# shieldSchematic.net
KiCad netlist of a schematic drawn in EAGLE
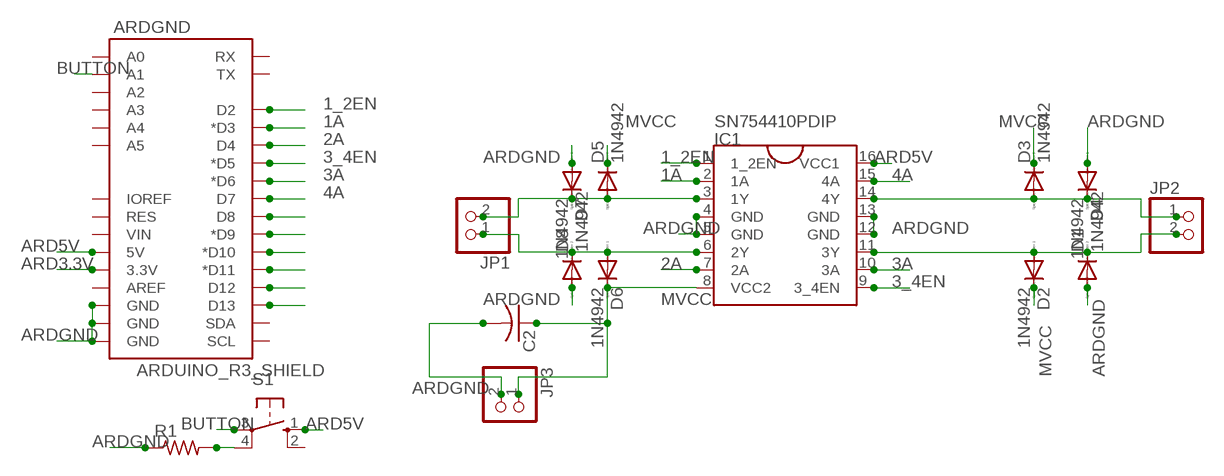
[diagram p0: schematic, sheet 1]

(export (version "E")
  (design (tool "Eeschema 10.0.6"))
  (components
    (comp (ref "ARDGND")
      (value "ARDUINO_R3_SHIELD")
      (footprint "eagle-import:UNO_R3_SHIELD")
      (libsource (lib "eagle-import") (part "ARDUINO_R3_SHIELD"))
    )
    (comp (ref "C2")
      (value "C-US025-024X044")
      (footprint "eagle-import:C025-024X044")
      (libsource (lib "eagle-import") (part "C-US025-024X044"))
    )
    (comp (ref "D1")
      (value "1N4942")
      (footprint "eagle-import:DO41-10")
      (libsource (lib "eagle-import") (part "1N4942"))
    )
    (comp (ref "D2")
      (value "1N4942")
      (footprint "eagle-import:DO41-10")
      (libsource (lib "eagle-import") (part "1N4942"))
    )
    (comp (ref "D3")
      (value "1N4942")
      (footprint "eagle-import:DO41-10")
      (libsource (lib "eagle-import") (part "1N4942"))
    )
    (comp (ref "D4")
      (value "1N4942")
      (footprint "eagle-import:DO41-10")
      (libsource (lib "eagle-import") (part "1N4942"))
    )
    (comp (ref "D5")
      (value "1N4942")
      (footprint "eagle-import:DO41-10")
      (libsource (lib "eagle-import") (part "1N4942"))
    )
    (comp (ref "D6")
      (value "1N4942")
      (footprint "eagle-import:DO41-10")
      (libsource (lib "eagle-import") (part "1N4942"))
    )
    (comp (ref "D7")
      (value "1N4942")
      (footprint "eagle-import:DO41-10")
      (libsource (lib "eagle-import") (part "1N4942"))
    )
    (comp (ref "D8")
      (value "1N4942")
      (footprint "eagle-import:DO41-10")
      (libsource (lib "eagle-import") (part "1N4942"))
    )
    (comp (ref "IC1")
      (value "SN754410PDIP")
      (footprint "eagle-import:DIL16")
      (libsource (lib "eagle-import") (part "SN754410PDIP"))
    )
    (comp (ref "JP1")
      (value "PINHD-1X2")
      (footprint "eagle-import:1X02")
      (libsource (lib "eagle-import") (part "PINHD-1X2"))
    )
    (comp (ref "JP2")
      (value "PINHD-1X2")
      (footprint "eagle-import:1X02")
      (libsource (lib "eagle-import") (part "PINHD-1X2"))
    )
    (comp (ref "JP3")
      (value "PINHD-1X2")
      (footprint "eagle-import:1X02")
      (libsource (lib "eagle-import") (part "PINHD-1X2"))
    )
    (comp (ref "R1")
      (value "R-US_0207/10")
      (footprint "eagle-import:0207_10")
      (libsource (lib "eagle-import") (part "R-US_0207/10"))
    )
    (comp (ref "S1")
      (value "40-XX")
      (footprint "eagle-import:B3F-40XX")
      (fields (field (name "MF") "OMRON COMPONENTS USA") (field (name "MPN") "B3F-4000"))
      (libsource (lib "eagle-import") (part "40-XX"))
    )
  )
  (nets
    (net (code "1") (name "/1A") (class "Default")
      (node (ref "ARDGND") (pin "D3") (pinfunction "*D3_D3") (pintype "bidirectional"))
      (node (ref "IC1") (pin "2") (pinfunction "1A_2") (pintype "bidirectional"))
    )
    (net (code "2") (name "/1_2EN") (class "Default")
      (node (ref "ARDGND") (pin "D2") (pinfunction "D2_D2") (pintype "bidirectional"))
      (node (ref "IC1") (pin "1") (pinfunction "1_2EN_1") (pintype "bidirectional"))
    )
    (net (code "3") (name "/2A") (class "Default")
      (node (ref "ARDGND") (pin "D4") (pinfunction "D4_D4") (pintype "bidirectional"))
      (node (ref "IC1") (pin "7") (pinfunction "2A_7") (pintype "bidirectional"))
    )
    (net (code "4") (name "/3A") (class "Default")
      (node (ref "ARDGND") (pin "D6") (pinfunction "*D6_D6") (pintype "bidirectional"))
      (node (ref "IC1") (pin "10") (pinfunction "3A_10") (pintype "bidirectional"))
    )
    (net (code "5") (name "/3_4EN") (class "Default")
      (node (ref "ARDGND") (pin "D5") (pinfunction "*D5_D5") (pintype "bidirectional"))
      (node (ref "IC1") (pin "9") (pinfunction "3_4EN_9") (pintype "bidirectional"))
    )
    (net (code "6") (name "/4A") (class "Default")
      (node (ref "ARDGND") (pin "D7") (pinfunction "D7_D7") (pintype "bidirectional"))
      (node (ref "IC1") (pin "15") (pinfunction "4A_15") (pintype "bidirectional"))
    )
    (net (code "7") (name "/ARD3.3V") (class "Default")
      (node (ref "ARDGND") (pin "3.3V") (pinfunction "3.3V_3.3V") (pintype "bidirectional"))
    )
    (net (code "8") (name "/ARD5V") (class "Default")
      (node (ref "ARDGND") (pin "5V") (pinfunction "5V_5V") (pintype "bidirectional"))
      (node (ref "IC1") (pin "16") (pinfunction "VCC1_16") (pintype "bidirectional"))
      (node (ref "S1") (pin "1") (pinfunction "S_1") (pintype "passive"))
    )
    (net (code "9") (name "/ARDGND") (class "Default")
      (node (ref "ARDGND") (pin "GND@0") (pinfunction "GND_GND@0") (pintype "bidirectional"))
      (node (ref "ARDGND") (pin "GND@1") (pinfunction "GND_GND@1") (pintype "bidirectional"))
      (node (ref "ARDGND") (pin "GND@2") (pinfunction "GND_GND@2") (pintype "bidirectional"))
      (node (ref "C2") (pin "2") (pinfunction "2_2") (pintype "passive"))
      (node (ref "D1") (pin "A") (pinfunction "A_A") (pintype "passive"))
      (node (ref "D4") (pin "A") (pinfunction "A_A") (pintype "passive"))
      (node (ref "D7") (pin "A") (pinfunction "A_A") (pintype "passive"))
      (node (ref "D8") (pin "A") (pinfunction "A_A") (pintype "passive"))
      (node (ref "IC1") (pin "12") (pinfunction "GND_12") (pintype "bidirectional"))
      (node (ref "IC1") (pin "13") (pinfunction "GND_13") (pintype "bidirectional"))
      (node (ref "IC1") (pin "4") (pinfunction "GND_4") (pintype "bidirectional"))
      (node (ref "IC1") (pin "5") (pinfunction "GND_5") (pintype "bidirectional"))
      (node (ref "JP3") (pin "2") (pinfunction "2_2") (pintype "passive"))
      (node (ref "R1") (pin "1") (pinfunction "1_1") (pintype "passive"))
    )
    (net (code "10") (name "/BUTTON") (class "Default")
      (node (ref "ARDGND") (pin "A1") (pinfunction "A1_A1") (pintype "bidirectional"))
      (node (ref "S1") (pin "3") (pinfunction "P_3") (pintype "passive"))
    )
    (net (code "11") (name "/MVCC") (class "Default")
      (node (ref "C2") (pin "1") (pinfunction "1_1") (pintype "passive"))
      (node (ref "D2") (pin "C") (pinfunction "C_C") (pintype "passive"))
      (node (ref "D3") (pin "C") (pinfunction "C_C") (pintype "passive"))
      (node (ref "D5") (pin "C") (pinfunction "C_C") (pintype "passive"))
      (node (ref "D6") (pin "C") (pinfunction "C_C") (pintype "passive"))
      (node (ref "IC1") (pin "8") (pinfunction "VCC2_8") (pintype "bidirectional"))
      (node (ref "JP3") (pin "1") (pinfunction "1_1") (pintype "passive"))
    )
    (net (code "12") (name "Net-(IC1-1Y)") (class "Default")
      (node (ref "D5") (pin "A") (pinfunction "A_A") (pintype "passive"))
      (node (ref "D7") (pin "C") (pinfunction "C_C") (pintype "passive"))
      (node (ref "IC1") (pin "3") (pinfunction "1Y_3") (pintype "bidirectional"))
      (node (ref "JP1") (pin "2") (pinfunction "2_2") (pintype "passive"))
    )
    (net (code "13") (name "Net-(IC1-2Y)") (class "Default")
      (node (ref "D6") (pin "A") (pinfunction "A_A") (pintype "passive"))
      (node (ref "D8") (pin "C") (pinfunction "C_C") (pintype "passive"))
      (node (ref "IC1") (pin "6") (pinfunction "2Y_6") (pintype "bidirectional"))
      (node (ref "JP1") (pin "1") (pinfunction "1_1") (pintype "passive"))
    )
    (net (code "14") (name "Net-(IC1-3Y)") (class "Default")
      (node (ref "D1") (pin "C") (pinfunction "C_C") (pintype "passive"))
      (node (ref "D2") (pin "A") (pinfunction "A_A") (pintype "passive"))
      (node (ref "IC1") (pin "11") (pinfunction "3Y_11") (pintype "bidirectional"))
      (node (ref "JP2") (pin "2") (pinfunction "2_2") (pintype "passive"))
    )
    (net (code "15") (name "Net-(IC1-4Y)") (class "Default")
      (node (ref "D3") (pin "A") (pinfunction "A_A") (pintype "passive"))
      (node (ref "D4") (pin "C") (pinfunction "C_C") (pintype "passive"))
      (node (ref "IC1") (pin "14") (pinfunction "4Y_14") (pintype "bidirectional"))
      (node (ref "JP2") (pin "1") (pinfunction "1_1") (pintype "passive"))
    )
    (net (code "16") (name "Net-(S1-P1)") (class "Default")
      (node (ref "R1") (pin "2") (pinfunction "2_2") (pintype "passive"))
      (node (ref "S1") (pin "4") (pinfunction "P1_4") (pintype "passive"))
    )
    (net (code "17") (name "unconnected-(ARDGND-*D9-PadD9)") (class "Default")
      (node (ref "ARDGND") (pin "D9") (pinfunction "*D9_D9") (pintype "bidirectional"))
    )
    (net (code "18") (name "unconnected-(ARDGND-*D10-PadD10)") (class "Default")
      (node (ref "ARDGND") (pin "D10") (pinfunction "*D10_D10") (pintype "bidirectional"))
    )
    (net (code "19") (name "unconnected-(ARDGND-*D11-PadD11)") (class "Default")
      (node (ref "ARDGND") (pin "D11") (pinfunction "*D11_D11") (pintype "bidirectional"))
    )
    (net (code "20") (name "unconnected-(ARDGND-PadA0)") (class "Default")
      (node (ref "ARDGND") (pin "A0") (pinfunction "A0_A0") (pintype "bidirectional"))
    )
    (net (code "21") (name "unconnected-(ARDGND-PadA2)") (class "Default")
      (node (ref "ARDGND") (pin "A2") (pinfunction "A2_A2") (pintype "bidirectional"))
    )
    (net (code "22") (name "unconnected-(ARDGND-PadA3)") (class "Default")
      (node (ref "ARDGND") (pin "A3") (pinfunction "A3_A3") (pintype "bidirectional"))
    )
    (net (code "23") (name "unconnected-(ARDGND-PadA4)") (class "Default")
      (node (ref "ARDGND") (pin "A4") (pinfunction "A4_A4") (pintype "bidirectional"))
    )
    (net (code "24") (name "unconnected-(ARDGND-PadA5)") (class "Default")
      (node (ref "ARDGND") (pin "A5") (pinfunction "A5_A5") (pintype "bidirectional"))
    )
    (net (code "25") (name "unconnected-(ARDGND-PadAREF)") (class "Default")
      (node (ref "ARDGND") (pin "AREF") (pinfunction "AREF_AREF") (pintype "bidirectional"))
    )
    (net (code "26") (name "unconnected-(ARDGND-PadD8)") (class "Default")
      (node (ref "ARDGND") (pin "D8") (pinfunction "D8_D8") (pintype "bidirectional"))
    )
    (net (code "27") (name "unconnected-(ARDGND-PadD12)") (class "Default")
      (node (ref "ARDGND") (pin "D12") (pinfunction "D12_D12") (pintype "bidirectional"))
    )
    (net (code "28") (name "unconnected-(ARDGND-PadD13)") (class "Default")
      (node (ref "ARDGND") (pin "D13") (pinfunction "D13_D13") (pintype "bidirectional"))
    )
    (net (code "29") (name "unconnected-(ARDGND-PadIOREF)") (class "Default")
      (node (ref "ARDGND") (pin "IOREF") (pinfunction "IOREF_IOREF") (pintype "bidirectional"))
    )
    (net (code "30") (name "unconnected-(ARDGND-PadRES)") (class "Default")
      (node (ref "ARDGND") (pin "RES") (pinfunction "RES_RES") (pintype "bidirectional"))
    )
    (net (code "31") (name "unconnected-(ARDGND-PadRX)") (class "Default")
      (node (ref "ARDGND") (pin "RX") (pinfunction "RX_RX") (pintype "bidirectional"))
    )
    (net (code "32") (name "unconnected-(ARDGND-PadSCL)") (class "Default")
      (node (ref "ARDGND") (pin "SCL") (pinfunction "SCL_SCL") (pintype "bidirectional"))
    )
    (net (code "33") (name "unconnected-(ARDGND-PadSDA)") (class "Default")
      (node (ref "ARDGND") (pin "SDA") (pinfunction "SDA_SDA") (pintype "bidirectional"))
    )
    (net (code "34") (name "unconnected-(ARDGND-PadTX)") (class "Default")
      (node (ref "ARDGND") (pin "TX") (pinfunction "TX_TX") (pintype "bidirectional"))
    )
    (net (code "35") (name "unconnected-(ARDGND-PadVIN)") (class "Default")
      (node (ref "ARDGND") (pin "VIN") (pinfunction "VIN_VIN") (pintype "bidirectional"))
    )
    (net (code "36") (name "unconnected-(S1-S1-Pad2)") (class "Default")
      (node (ref "S1") (pin "2") (pinfunction "S1_2") (pintype "passive"))
    )
  )
)
